# S05_SOM2_A_B.net
KiCad netlist of a schematic drawn in Altium Designer
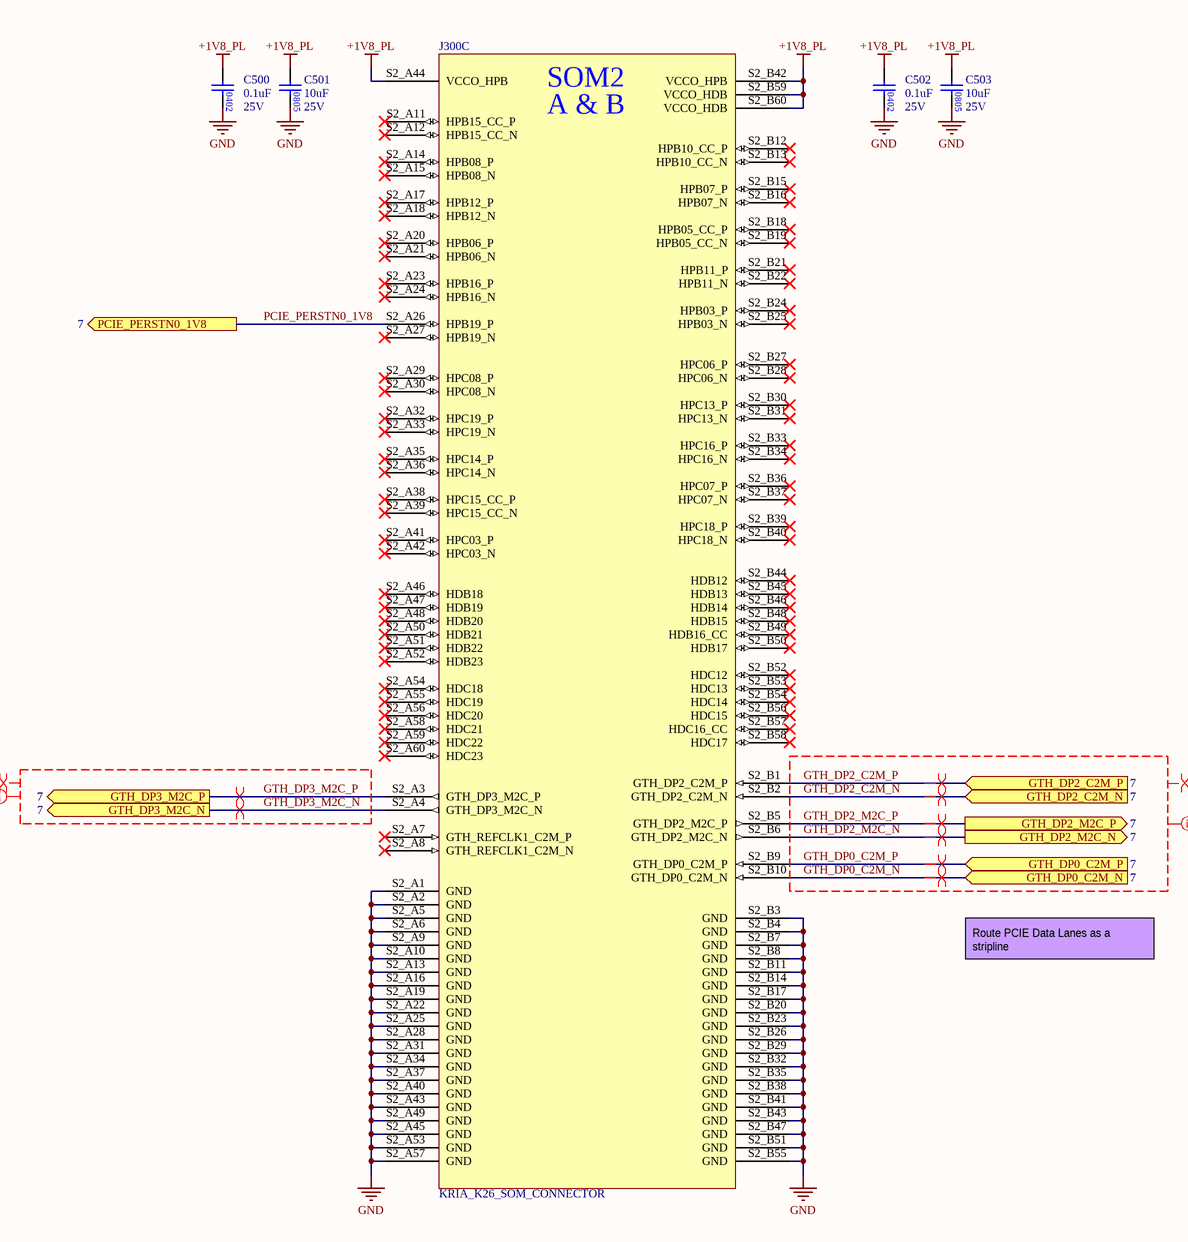
[diagram p0: S05_SOM2_A_B.SchDoc]

(export (version "E")
  (design (tool "Eeschema 10.0.6"))
  (components
    (comp (ref "C500")
      (value "0.1uF")
      (footprint "CAP0402")
      (description "CAP CER 0.1UF 25V X5R 0402")
      (fields
        (field (name "MANUFACTURER") "Samsung Electro-Mechanics")
        (field (name "TOLERANCE") "10%")
        (field (name "VOLTAGE RATING") "25V")
      )
      (libsource (lib "OpenCore_Sch_Lib") (part "CAP_CL05A104KA5NNNC"))
    )
    (comp (ref "C501")
      (value "10uF")
      (footprint "CAP0805")
      (description "CAP CER 10UF 25V X5R 0805")
      (fields
        (field (name "MANUFACTURER") "Samsung Electro-Mechanics")
        (field (name "TOLERANCE") "10%")
        (field (name "VOLTAGE RATING") "25V")
      )
      (libsource (lib "OpenCore_Sch_Lib") (part "CAP_CL21A106KAYNNNE"))
    )
    (comp (ref "C502")
      (value "0.1uF")
      (footprint "CAP0402")
      (description "CAP CER 0.1UF 25V X5R 0402")
      (fields
        (field (name "MANUFACTURER") "Samsung Electro-Mechanics")
        (field (name "TOLERANCE") "10%")
        (field (name "VOLTAGE RATING") "25V")
      )
      (libsource (lib "OpenCore_Sch_Lib") (part "CAP_CL05A104KA5NNNC"))
    )
    (comp (ref "C503")
      (value "10uF")
      (footprint "CAP0805")
      (description "CAP CER 10UF 25V X5R 0805")
      (fields
        (field (name "MANUFACTURER") "Samsung Electro-Mechanics")
        (field (name "TOLERANCE") "10%")
        (field (name "VOLTAGE RATING") "25V")
      )
      (libsource (lib "OpenCore_Sch_Lib") (part "CAP_CL21A106KAYNNNE"))
    )
    (comp (ref "J300")
      (value "KRIA_K26_SOM_CONNECTOR")
      (footprint "KRIA_K26_SOM")
      (description "2 x 240 pos Samtec REF-226081-01")
      (fields
        (field (name "MANUFACTURER") "Samtec")
        (field (name "MANUFACTURER PART NUMBER") "REF-226081-01")
      )
      (libsource (lib "OpenCore_Sch_Lib") (part "KRIA_K26_SOM"))
    )
  )
  (nets
    (net (code "1") (name "+1V8_PL") (class "Default")
      (node (ref "C500") (pin "1") (pinfunction "1_1") (pintype "passive"))
      (node (ref "C501") (pin "1") (pinfunction "1_1") (pintype "passive"))
      (node (ref "C502") (pin "1") (pinfunction "1_1") (pintype "passive"))
      (node (ref "C503") (pin "1") (pinfunction "1_1") (pintype "passive"))
      (node (ref "J300") (pin "S2_A44") (pinfunction "VCCO_HPB_S2_A44") (pintype "power_in"))
      (node (ref "J300") (pin "S2_B42") (pinfunction "VCCO_HPB_S2_B42") (pintype "power_in"))
      (node (ref "J300") (pin "S2_B59") (pinfunction "VCCO_HDB_S2_B59") (pintype "power_in"))
      (node (ref "J300") (pin "S2_B60") (pinfunction "VCCO_HDB_S2_B60") (pintype "power_in"))
    )
    (net (code "2") (name "/GTH_DP0_C2M_N") (class "Default")
      (node (ref "J300") (pin "S2_B10") (pinfunction "GTH_DP0_C2M_N_S2_B10") (pintype "input"))
    )
    (net (code "3") (name "/GTH_DP0_C2M_P") (class "Default")
      (node (ref "J300") (pin "S2_B9") (pinfunction "GTH_DP0_C2M_P_S2_B9") (pintype "input"))
    )
    (net (code "4") (name "/GTH_DP2_C2M_N") (class "Default")
      (node (ref "J300") (pin "S2_B2") (pinfunction "GTH_DP2_C2M_N_S2_B2") (pintype "input"))
    )
    (net (code "5") (name "/GTH_DP2_C2M_P") (class "Default")
      (node (ref "J300") (pin "S2_B1") (pinfunction "GTH_DP2_C2M_P_S2_B1") (pintype "input"))
    )
    (net (code "6") (name "/GTH_DP2_M2C_N") (class "Default")
      (node (ref "J300") (pin "S2_B6") (pinfunction "GTH_DP2_M2C_N_S2_B6") (pintype "output"))
    )
    (net (code "7") (name "/GTH_DP2_M2C_P") (class "Default")
      (node (ref "J300") (pin "S2_B5") (pinfunction "GTH_DP2_M2C_P_S2_B5") (pintype "output"))
    )
    (net (code "8") (name "/GTH_DP3_M2C_N") (class "Default")
      (node (ref "J300") (pin "S2_A4") (pinfunction "GTH_DP3_M2C_N_S2_A4") (pintype "output"))
    )
    (net (code "9") (name "/GTH_DP3_M2C_P") (class "Default")
      (node (ref "J300") (pin "S2_A3") (pinfunction "GTH_DP3_M2C_P_S2_A3") (pintype "output"))
    )
    (net (code "10") (name "/PCIE_PERSTN0_1V8") (class "Default")
      (node (ref "J300") (pin "S2_A26") (pinfunction "HPB19_P_S2_A26") (pintype "bidirectional"))
    )
    (net (code "11") (name "GND") (class "Default")
      (node (ref "C500") (pin "2") (pinfunction "2_2") (pintype "passive"))
      (node (ref "C501") (pin "2") (pinfunction "2_2") (pintype "passive"))
      (node (ref "C502") (pin "2") (pinfunction "2_2") (pintype "passive"))
      (node (ref "C503") (pin "2") (pinfunction "2_2") (pintype "passive"))
      (node (ref "J300") (pin "S2_A1") (pinfunction "GND_S2_A1") (pintype "power_in"))
      (node (ref "J300") (pin "S2_A10") (pinfunction "GND_S2_A10") (pintype "power_in"))
      (node (ref "J300") (pin "S2_A13") (pinfunction "GND_S2_A13") (pintype "power_in"))
      (node (ref "J300") (pin "S2_A16") (pinfunction "GND_S2_A16") (pintype "power_in"))
      (node (ref "J300") (pin "S2_A19") (pinfunction "GND_S2_A19") (pintype "power_in"))
      (node (ref "J300") (pin "S2_A2") (pinfunction "GND_S2_A2") (pintype "power_in"))
      (node (ref "J300") (pin "S2_A22") (pinfunction "GND_S2_A22") (pintype "power_in"))
      (node (ref "J300") (pin "S2_A25") (pinfunction "GND_S2_A25") (pintype "power_in"))
      (node (ref "J300") (pin "S2_A28") (pinfunction "GND_S2_A28") (pintype "power_in"))
      (node (ref "J300") (pin "S2_A31") (pinfunction "GND_S2_A31") (pintype "power_in"))
      (node (ref "J300") (pin "S2_A34") (pinfunction "GND_S2_A34") (pintype "power_in"))
      (node (ref "J300") (pin "S2_A37") (pinfunction "GND_S2_A37") (pintype "power_in"))
      (node (ref "J300") (pin "S2_A40") (pinfunction "GND_S2_A40") (pintype "power_in"))
      (node (ref "J300") (pin "S2_A43") (pinfunction "GND_S2_A43") (pintype "power_in"))
      (node (ref "J300") (pin "S2_A45") (pinfunction "GND_S2_A45") (pintype "power_in"))
      (node (ref "J300") (pin "S2_A49") (pinfunction "GND_S2_A49") (pintype "power_in"))
      (node (ref "J300") (pin "S2_A5") (pinfunction "GND_S2_A5") (pintype "power_in"))
      (node (ref "J300") (pin "S2_A53") (pinfunction "GND_S2_A53") (pintype "power_in"))
      (node (ref "J300") (pin "S2_A57") (pinfunction "GND_S2_A57") (pintype "power_in"))
      (node (ref "J300") (pin "S2_A6") (pinfunction "GND_S2_A6") (pintype "power_in"))
      (node (ref "J300") (pin "S2_A9") (pinfunction "GND_S2_A9") (pintype "power_in"))
      (node (ref "J300") (pin "S2_B11") (pinfunction "GND_S2_B11") (pintype "power_in"))
      (node (ref "J300") (pin "S2_B14") (pinfunction "GND_S2_B14") (pintype "power_in"))
      (node (ref "J300") (pin "S2_B17") (pinfunction "GND_S2_B17") (pintype "power_in"))
      (node (ref "J300") (pin "S2_B20") (pinfunction "GND_S2_B20") (pintype "power_in"))
      (node (ref "J300") (pin "S2_B23") (pinfunction "GND_S2_B23") (pintype "power_in"))
      (node (ref "J300") (pin "S2_B26") (pinfunction "GND_S2_B26") (pintype "power_in"))
      (node (ref "J300") (pin "S2_B29") (pinfunction "GND_S2_B29") (pintype "power_in"))
      (node (ref "J300") (pin "S2_B3") (pinfunction "GND_S2_B3") (pintype "power_in"))
      (node (ref "J300") (pin "S2_B32") (pinfunction "GND_S2_B32") (pintype "power_in"))
      (node (ref "J300") (pin "S2_B35") (pinfunction "GND_S2_B35") (pintype "power_in"))
      (node (ref "J300") (pin "S2_B38") (pinfunction "GND_S2_B38") (pintype "power_in"))
      (node (ref "J300") (pin "S2_B4") (pinfunction "GND_S2_B4") (pintype "power_in"))
      (node (ref "J300") (pin "S2_B41") (pinfunction "GND_S2_B41") (pintype "power_in"))
      (node (ref "J300") (pin "S2_B43") (pinfunction "GND_S2_B43") (pintype "power_in"))
      (node (ref "J300") (pin "S2_B47") (pinfunction "GND_S2_B47") (pintype "power_in"))
      (node (ref "J300") (pin "S2_B51") (pinfunction "GND_S2_B51") (pintype "power_in"))
      (node (ref "J300") (pin "S2_B55") (pinfunction "GND_S2_B55") (pintype "power_in"))
      (node (ref "J300") (pin "S2_B7") (pinfunction "GND_S2_B7") (pintype "power_in"))
      (node (ref "J300") (pin "S2_B8") (pinfunction "GND_S2_B8") (pintype "power_in"))
    )
    (net (code "12") (name "unconnected-(J300C-GTH_REFCLK1_C2M_N-PadS2_A8)") (class "Default")
      (node (ref "J300") (pin "S2_A8") (pinfunction "GTH_REFCLK1_C2M_N_S2_A8") (pintype "input+no_connect"))
    )
    (net (code "13") (name "unconnected-(J300C-GTH_REFCLK1_C2M_P-PadS2_A7)") (class "Default")
      (node (ref "J300") (pin "S2_A7") (pinfunction "GTH_REFCLK1_C2M_P_S2_A7") (pintype "input+no_connect"))
    )
    (net (code "14") (name "unconnected-(J300C-HDB12-PadS2_B44)") (class "Default")
      (node (ref "J300") (pin "S2_B44") (pinfunction "HDB12_S2_B44") (pintype "bidirectional+no_connect"))
    )
    (net (code "15") (name "unconnected-(J300C-HDB13-PadS2_B45)") (class "Default")
      (node (ref "J300") (pin "S2_B45") (pinfunction "HDB13_S2_B45") (pintype "bidirectional+no_connect"))
    )
    (net (code "16") (name "unconnected-(J300C-HDB14-PadS2_B46)") (class "Default")
      (node (ref "J300") (pin "S2_B46") (pinfunction "HDB14_S2_B46") (pintype "bidirectional+no_connect"))
    )
    (net (code "17") (name "unconnected-(J300C-HDB15-PadS2_B48)") (class "Default")
      (node (ref "J300") (pin "S2_B48") (pinfunction "HDB15_S2_B48") (pintype "bidirectional+no_connect"))
    )
    (net (code "18") (name "unconnected-(J300C-HDB16_CC-PadS2_B49)") (class "Default")
      (node (ref "J300") (pin "S2_B49") (pinfunction "HDB16_CC_S2_B49") (pintype "bidirectional+no_connect"))
    )
    (net (code "19") (name "unconnected-(J300C-HDB17-PadS2_B50)") (class "Default")
      (node (ref "J300") (pin "S2_B50") (pinfunction "HDB17_S2_B50") (pintype "bidirectional+no_connect"))
    )
    (net (code "20") (name "unconnected-(J300C-HDB18-PadS2_A46)") (class "Default")
      (node (ref "J300") (pin "S2_A46") (pinfunction "HDB18_S2_A46") (pintype "bidirectional+no_connect"))
    )
    (net (code "21") (name "unconnected-(J300C-HDB19-PadS2_A47)") (class "Default")
      (node (ref "J300") (pin "S2_A47") (pinfunction "HDB19_S2_A47") (pintype "bidirectional+no_connect"))
    )
    (net (code "22") (name "unconnected-(J300C-HDB20-PadS2_A48)") (class "Default")
      (node (ref "J300") (pin "S2_A48") (pinfunction "HDB20_S2_A48") (pintype "bidirectional+no_connect"))
    )
    (net (code "23") (name "unconnected-(J300C-HDB21-PadS2_A50)") (class "Default")
      (node (ref "J300") (pin "S2_A50") (pinfunction "HDB21_S2_A50") (pintype "bidirectional+no_connect"))
    )
    (net (code "24") (name "unconnected-(J300C-HDB22-PadS2_A51)") (class "Default")
      (node (ref "J300") (pin "S2_A51") (pinfunction "HDB22_S2_A51") (pintype "bidirectional+no_connect"))
    )
    (net (code "25") (name "unconnected-(J300C-HDB23-PadS2_A52)") (class "Default")
      (node (ref "J300") (pin "S2_A52") (pinfunction "HDB23_S2_A52") (pintype "bidirectional+no_connect"))
    )
    (net (code "26") (name "unconnected-(J300C-HDC12-PadS2_B52)") (class "Default")
      (node (ref "J300") (pin "S2_B52") (pinfunction "HDC12_S2_B52") (pintype "bidirectional+no_connect"))
    )
    (net (code "27") (name "unconnected-(J300C-HDC13-PadS2_B53)") (class "Default")
      (node (ref "J300") (pin "S2_B53") (pinfunction "HDC13_S2_B53") (pintype "bidirectional+no_connect"))
    )
    (net (code "28") (name "unconnected-(J300C-HDC14-PadS2_B54)") (class "Default")
      (node (ref "J300") (pin "S2_B54") (pinfunction "HDC14_S2_B54") (pintype "bidirectional+no_connect"))
    )
    (net (code "29") (name "unconnected-(J300C-HDC15-PadS2_B56)") (class "Default")
      (node (ref "J300") (pin "S2_B56") (pinfunction "HDC15_S2_B56") (pintype "bidirectional+no_connect"))
    )
    (net (code "30") (name "unconnected-(J300C-HDC16_CC-PadS2_B57)") (class "Default")
      (node (ref "J300") (pin "S2_B57") (pinfunction "HDC16_CC_S2_B57") (pintype "bidirectional+no_connect"))
    )
    (net (code "31") (name "unconnected-(J300C-HDC17-PadS2_B58)") (class "Default")
      (node (ref "J300") (pin "S2_B58") (pinfunction "HDC17_S2_B58") (pintype "bidirectional+no_connect"))
    )
    (net (code "32") (name "unconnected-(J300C-HDC18-PadS2_A54)") (class "Default")
      (node (ref "J300") (pin "S2_A54") (pinfunction "HDC18_S2_A54") (pintype "bidirectional+no_connect"))
    )
    (net (code "33") (name "unconnected-(J300C-HDC19-PadS2_A55)") (class "Default")
      (node (ref "J300") (pin "S2_A55") (pinfunction "HDC19_S2_A55") (pintype "bidirectional+no_connect"))
    )
    (net (code "34") (name "unconnected-(J300C-HDC20-PadS2_A56)") (class "Default")
      (node (ref "J300") (pin "S2_A56") (pinfunction "HDC20_S2_A56") (pintype "bidirectional+no_connect"))
    )
    (net (code "35") (name "unconnected-(J300C-HDC21-PadS2_A58)") (class "Default")
      (node (ref "J300") (pin "S2_A58") (pinfunction "HDC21_S2_A58") (pintype "bidirectional+no_connect"))
    )
    (net (code "36") (name "unconnected-(J300C-HDC22-PadS2_A59)") (class "Default")
      (node (ref "J300") (pin "S2_A59") (pinfunction "HDC22_S2_A59") (pintype "bidirectional+no_connect"))
    )
    (net (code "37") (name "unconnected-(J300C-HDC23-PadS2_A60)") (class "Default")
      (node (ref "J300") (pin "S2_A60") (pinfunction "HDC23_S2_A60") (pintype "bidirectional+no_connect"))
    )
    (net (code "38") (name "unconnected-(J300C-HPB03_N-PadS2_B25)") (class "Default")
      (node (ref "J300") (pin "S2_B25") (pinfunction "HPB03_N_S2_B25") (pintype "bidirectional+no_connect"))
    )
    (net (code "39") (name "unconnected-(J300C-HPB03_P-PadS2_B24)") (class "Default")
      (node (ref "J300") (pin "S2_B24") (pinfunction "HPB03_P_S2_B24") (pintype "bidirectional+no_connect"))
    )
    (net (code "40") (name "unconnected-(J300C-HPB05_CC_N-PadS2_B19)") (class "Default")
      (node (ref "J300") (pin "S2_B19") (pinfunction "HPB05_CC_N_S2_B19") (pintype "bidirectional+no_connect"))
    )
    (net (code "41") (name "unconnected-(J300C-HPB05_CC_P-PadS2_B18)") (class "Default")
      (node (ref "J300") (pin "S2_B18") (pinfunction "HPB05_CC_P_S2_B18") (pintype "bidirectional+no_connect"))
    )
    (net (code "42") (name "unconnected-(J300C-HPB06_N-PadS2_A21)") (class "Default")
      (node (ref "J300") (pin "S2_A21") (pinfunction "HPB06_N_S2_A21") (pintype "bidirectional+no_connect"))
    )
    (net (code "43") (name "unconnected-(J300C-HPB06_P-PadS2_A20)") (class "Default")
      (node (ref "J300") (pin "S2_A20") (pinfunction "HPB06_P_S2_A20") (pintype "bidirectional+no_connect"))
    )
    (net (code "44") (name "unconnected-(J300C-HPB07_N-PadS2_B16)") (class "Default")
      (node (ref "J300") (pin "S2_B16") (pinfunction "HPB07_N_S2_B16") (pintype "bidirectional+no_connect"))
    )
    (net (code "45") (name "unconnected-(J300C-HPB07_P-PadS2_B15)") (class "Default")
      (node (ref "J300") (pin "S2_B15") (pinfunction "HPB07_P_S2_B15") (pintype "bidirectional+no_connect"))
    )
    (net (code "46") (name "unconnected-(J300C-HPB08_N-PadS2_A15)") (class "Default")
      (node (ref "J300") (pin "S2_A15") (pinfunction "HPB08_N_S2_A15") (pintype "bidirectional+no_connect"))
    )
    (net (code "47") (name "unconnected-(J300C-HPB08_P-PadS2_A14)") (class "Default")
      (node (ref "J300") (pin "S2_A14") (pinfunction "HPB08_P_S2_A14") (pintype "bidirectional+no_connect"))
    )
    (net (code "48") (name "unconnected-(J300C-HPB10_CC_N-PadS2_B13)") (class "Default")
      (node (ref "J300") (pin "S2_B13") (pinfunction "HPB10_CC_N_S2_B13") (pintype "bidirectional+no_connect"))
    )
    (net (code "49") (name "unconnected-(J300C-HPB10_CC_P-PadS2_B12)") (class "Default")
      (node (ref "J300") (pin "S2_B12") (pinfunction "HPB10_CC_P_S2_B12") (pintype "bidirectional+no_connect"))
    )
    (net (code "50") (name "unconnected-(J300C-HPB11_N-PadS2_B22)") (class "Default")
      (node (ref "J300") (pin "S2_B22") (pinfunction "HPB11_N_S2_B22") (pintype "bidirectional+no_connect"))
    )
    (net (code "51") (name "unconnected-(J300C-HPB11_P-PadS2_B21)") (class "Default")
      (node (ref "J300") (pin "S2_B21") (pinfunction "HPB11_P_S2_B21") (pintype "bidirectional+no_connect"))
    )
    (net (code "52") (name "unconnected-(J300C-HPB12_N-PadS2_A18)") (class "Default")
      (node (ref "J300") (pin "S2_A18") (pinfunction "HPB12_N_S2_A18") (pintype "bidirectional+no_connect"))
    )
    (net (code "53") (name "unconnected-(J300C-HPB12_P-PadS2_A17)") (class "Default")
      (node (ref "J300") (pin "S2_A17") (pinfunction "HPB12_P_S2_A17") (pintype "bidirectional+no_connect"))
    )
    (net (code "54") (name "unconnected-(J300C-HPB15_CC_N-PadS2_A12)") (class "Default")
      (node (ref "J300") (pin "S2_A12") (pinfunction "HPB15_CC_N_S2_A12") (pintype "bidirectional+no_connect"))
    )
    (net (code "55") (name "unconnected-(J300C-HPB15_CC_P-PadS2_A11)") (class "Default")
      (node (ref "J300") (pin "S2_A11") (pinfunction "HPB15_CC_P_S2_A11") (pintype "bidirectional+no_connect"))
    )
    (net (code "56") (name "unconnected-(J300C-HPB16_N-PadS2_A24)") (class "Default")
      (node (ref "J300") (pin "S2_A24") (pinfunction "HPB16_N_S2_A24") (pintype "bidirectional+no_connect"))
    )
    (net (code "57") (name "unconnected-(J300C-HPB16_P-PadS2_A23)") (class "Default")
      (node (ref "J300") (pin "S2_A23") (pinfunction "HPB16_P_S2_A23") (pintype "bidirectional+no_connect"))
    )
    (net (code "58") (name "unconnected-(J300C-HPB19_N-PadS2_A27)") (class "Default")
      (node (ref "J300") (pin "S2_A27") (pinfunction "HPB19_N_S2_A27") (pintype "bidirectional+no_connect"))
    )
    (net (code "59") (name "unconnected-(J300C-HPC03_N-PadS2_A42)") (class "Default")
      (node (ref "J300") (pin "S2_A42") (pinfunction "HPC03_N_S2_A42") (pintype "bidirectional+no_connect"))
    )
    (net (code "60") (name "unconnected-(J300C-HPC03_P-PadS2_A41)") (class "Default")
      (node (ref "J300") (pin "S2_A41") (pinfunction "HPC03_P_S2_A41") (pintype "bidirectional+no_connect"))
    )
    (net (code "61") (name "unconnected-(J300C-HPC06_N-PadS2_B28)") (class "Default")
      (node (ref "J300") (pin "S2_B28") (pinfunction "HPC06_N_S2_B28") (pintype "bidirectional+no_connect"))
    )
    (net (code "62") (name "unconnected-(J300C-HPC06_P-PadS2_B27)") (class "Default")
      (node (ref "J300") (pin "S2_B27") (pinfunction "HPC06_P_S2_B27") (pintype "bidirectional+no_connect"))
    )
    (net (code "63") (name "unconnected-(J300C-HPC07_N-PadS2_B37)") (class "Default")
      (node (ref "J300") (pin "S2_B37") (pinfunction "HPC07_N_S2_B37") (pintype "bidirectional+no_connect"))
    )
    (net (code "64") (name "unconnected-(J300C-HPC07_P-PadS2_B36)") (class "Default")
      (node (ref "J300") (pin "S2_B36") (pinfunction "HPC07_P_S2_B36") (pintype "bidirectional+no_connect"))
    )
    (net (code "65") (name "unconnected-(J300C-HPC08_N-PadS2_A30)") (class "Default")
      (node (ref "J300") (pin "S2_A30") (pinfunction "HPC08_N_S2_A30") (pintype "bidirectional+no_connect"))
    )
    (net (code "66") (name "unconnected-(J300C-HPC08_P-PadS2_A29)") (class "Default")
      (node (ref "J300") (pin "S2_A29") (pinfunction "HPC08_P_S2_A29") (pintype "bidirectional+no_connect"))
    )
    (net (code "67") (name "unconnected-(J300C-HPC13_N-PadS2_B31)") (class "Default")
      (node (ref "J300") (pin "S2_B31") (pinfunction "HPC13_N_S2_B31") (pintype "bidirectional+no_connect"))
    )
    (net (code "68") (name "unconnected-(J300C-HPC13_P-PadS2_B30)") (class "Default")
      (node (ref "J300") (pin "S2_B30") (pinfunction "HPC13_P_S2_B30") (pintype "bidirectional+no_connect"))
    )
    (net (code "69") (name "unconnected-(J300C-HPC14_N-PadS2_A36)") (class "Default")
      (node (ref "J300") (pin "S2_A36") (pinfunction "HPC14_N_S2_A36") (pintype "bidirectional+no_connect"))
    )
    (net (code "70") (name "unconnected-(J300C-HPC14_P-PadS2_A35)") (class "Default")
      (node (ref "J300") (pin "S2_A35") (pinfunction "HPC14_P_S2_A35") (pintype "bidirectional+no_connect"))
    )
    (net (code "71") (name "unconnected-(J300C-HPC15_CC_N-PadS2_A39)") (class "Default")
      (node (ref "J300") (pin "S2_A39") (pinfunction "HPC15_CC_N_S2_A39") (pintype "bidirectional+no_connect"))
    )
    (net (code "72") (name "unconnected-(J300C-HPC15_CC_P-PadS2_A38)") (class "Default")
      (node (ref "J300") (pin "S2_A38") (pinfunction "HPC15_CC_P_S2_A38") (pintype "bidirectional+no_connect"))
    )
    (net (code "73") (name "unconnected-(J300C-HPC16_N-PadS2_B34)") (class "Default")
      (node (ref "J300") (pin "S2_B34") (pinfunction "HPC16_N_S2_B34") (pintype "bidirectional+no_connect"))
    )
    (net (code "74") (name "unconnected-(J300C-HPC16_P-PadS2_B33)") (class "Default")
      (node (ref "J300") (pin "S2_B33") (pinfunction "HPC16_P_S2_B33") (pintype "bidirectional+no_connect"))
    )
    (net (code "75") (name "unconnected-(J300C-HPC18_N-PadS2_B40)") (class "Default")
      (node (ref "J300") (pin "S2_B40") (pinfunction "HPC18_N_S2_B40") (pintype "bidirectional+no_connect"))
    )
    (net (code "76") (name "unconnected-(J300C-HPC18_P-PadS2_B39)") (class "Default")
      (node (ref "J300") (pin "S2_B39") (pinfunction "HPC18_P_S2_B39") (pintype "bidirectional+no_connect"))
    )
    (net (code "77") (name "unconnected-(J300C-HPC19_N-PadS2_A33)") (class "Default")
      (node (ref "J300") (pin "S2_A33") (pinfunction "HPC19_N_S2_A33") (pintype "bidirectional+no_connect"))
    )
    (net (code "78") (name "unconnected-(J300C-HPC19_P-PadS2_A32)") (class "Default")
      (node (ref "J300") (pin "S2_A32") (pinfunction "HPC19_P_S2_A32") (pintype "bidirectional+no_connect"))
    )
  )
)
